# 2.net
KiCad netlist of a schematic drawn in Altium Designer
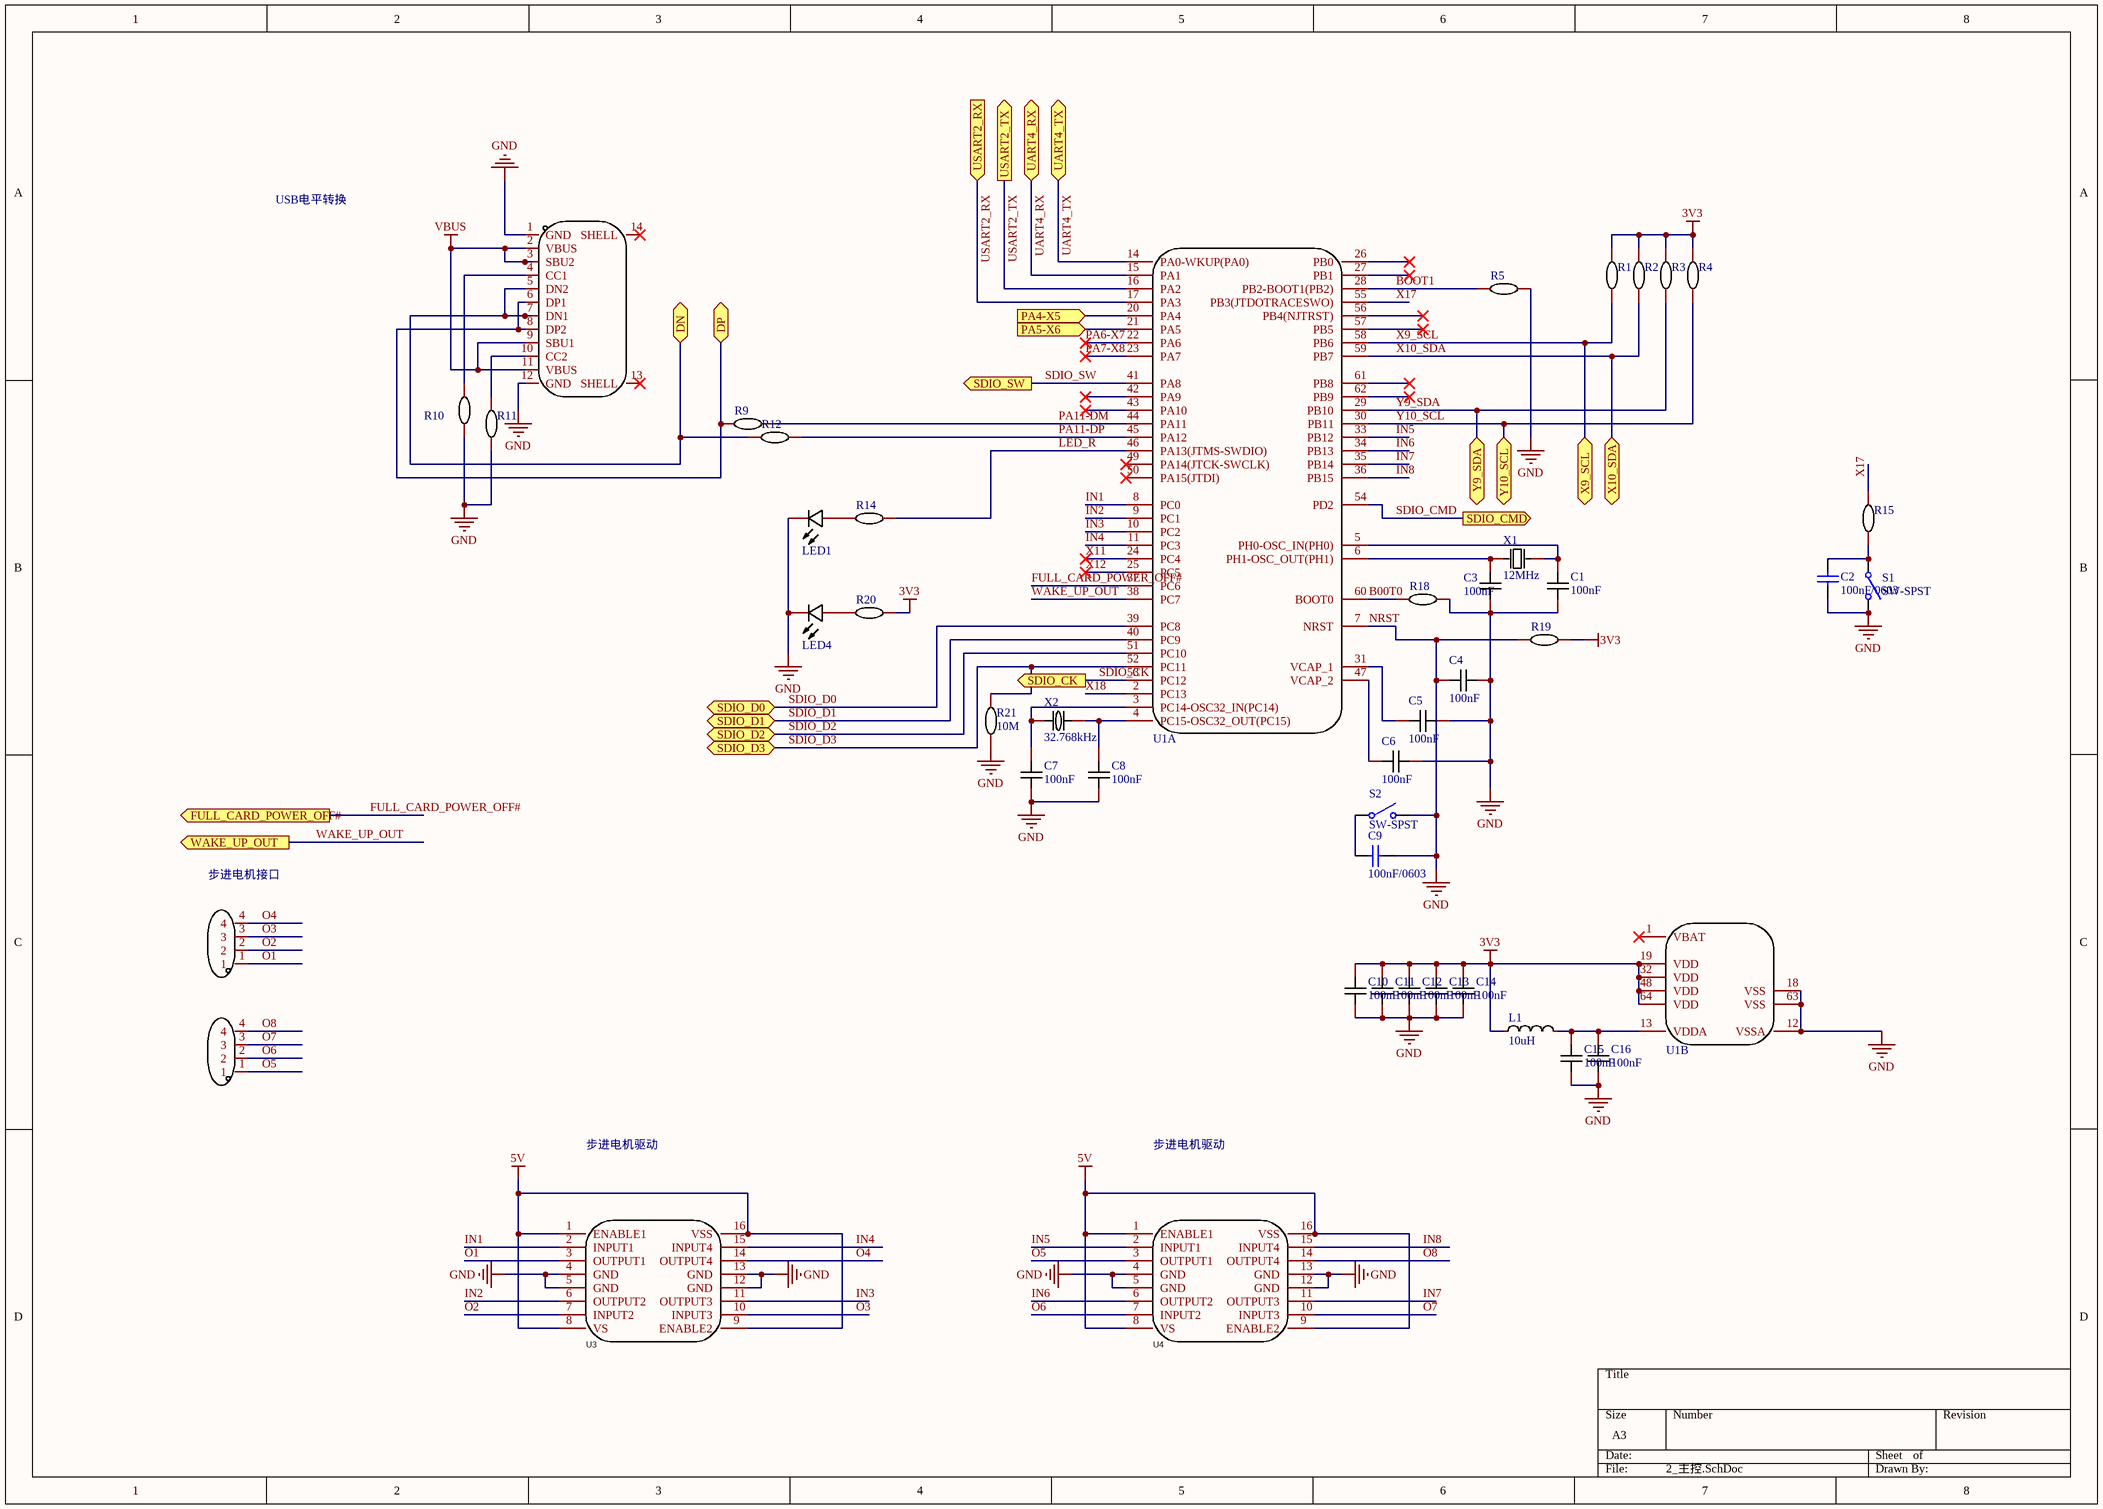
[diagram p0: 2_主控.SchDoc]

(export (version "E")
  (design (tool "Eeschema 10.0.6"))
  (components
    (comp (ref "C1")
      (value "100nF")
      (footprint "0603C")
      (fields (field (name "NAME") "100nF"))
      (libsource (lib "5_CPU_TF卡.schdoc") (part "CAP_0603"))
    )
    (comp (ref "C2")
      (value "100nF/0603")
      (footprint "0603C")
      (description "Capacitor")
      (fields (field (name "PUBLISHER") "Altium Limited"))
      (libsource (lib "MyComponents_v2.5") (part "Cap"))
    )
    (comp (ref "C3")
      (value "100nF")
      (footprint "0603C")
      (fields (field (name "NAME") "100nF"))
      (libsource (lib "5_CPU_TF卡.schdoc") (part "CAP_0603"))
    )
    (comp (ref "C4")
      (value "100nF")
      (footprint "0603C")
      (fields (field (name "NAME") "100nF"))
      (libsource (lib "5_CPU_TF卡.schdoc") (part "CAP_0603"))
    )
    (comp (ref "C5")
      (value "100nF")
      (footprint "0603C")
      (fields (field (name "NAME") "100nF"))
      (libsource (lib "5_CPU_TF卡.schdoc") (part "CAP_0603"))
    )
    (comp (ref "C6")
      (value "100nF")
      (footprint "0603C")
      (fields (field (name "NAME") "100nF"))
      (libsource (lib "5_CPU_TF卡.schdoc") (part "CAP_0603"))
    )
    (comp (ref "C7")
      (value "100nF")
      (footprint "0603C")
      (fields (field (name "NAME") "100nF"))
      (libsource (lib "5_CPU_TF卡.schdoc") (part "CAP_0603"))
    )
    (comp (ref "C8")
      (value "100nF")
      (footprint "0603C")
      (fields (field (name "NAME") "100nF"))
      (libsource (lib "5_CPU_TF卡.schdoc") (part "CAP_0603"))
    )
    (comp (ref "C9")
      (value "100nF/0603")
      (footprint "0603C")
      (description "Capacitor")
      (fields (field (name "PUBLISHER") "Altium Limited"))
      (libsource (lib "MyComponents_v2.5") (part "Cap"))
    )
    (comp (ref "C10")
      (value "100nF")
      (footprint "0402C")
      (fields (field (name "NAME") "100nF"))
      (libsource (lib "5_CPU_TF卡.schdoc") (part "CAP_0603"))
    )
    (comp (ref "C11")
      (value "100nF")
      (footprint "0402C")
      (fields (field (name "NAME") "100nF"))
      (libsource (lib "5_CPU_TF卡.schdoc") (part "CAP_0603"))
    )
    (comp (ref "C12")
      (value "100nF")
      (footprint "0402C")
      (fields (field (name "NAME") "100nF"))
      (libsource (lib "5_CPU_TF卡.schdoc") (part "CAP_0603"))
    )
    (comp (ref "C13")
      (value "100nF")
      (footprint "0402C")
      (fields (field (name "NAME") "100nF"))
      (libsource (lib "5_CPU_TF卡.schdoc") (part "CAP_0603"))
    )
    (comp (ref "C14")
      (value "100nF")
      (footprint "0402C")
      (fields (field (name "NAME") "100nF"))
      (libsource (lib "5_CPU_TF卡.schdoc") (part "CAP_0603"))
    )
    (comp (ref "C15")
      (value "100nF")
      (footprint "0402C")
      (fields (field (name "NAME") "100nF"))
      (libsource (lib "5_CPU_TF卡.schdoc") (part "CAP_0603"))
    )
    (comp (ref "C16")
      (value "100nF")
      (footprint "0402C")
      (fields (field (name "NAME") "100nF"))
      (libsource (lib "5_CPU_TF卡.schdoc") (part "CAP_0603"))
    )
    (comp (ref "CN1")
      (value "HC-XHB-4A")
      (footprint "CONN-TH_4P-P2.50_HCTL_HC-XHB-4A")
      (libsource (lib "HC-XHB-4A1_HC-XHB-4A.schdoc") (part "HC-XHB-4A"))
    )
    (comp (ref "CN2")
      (value "HC-XHB-4A")
      (footprint "CONN-TH_4P-P2.50_HCTL_HC-XHB-4A")
      (libsource (lib "HC-XHB-4A1_HC-XHB-4A.schdoc") (part "HC-XHB-4A"))
    )
    (comp (ref "L1")
      (value "10uH")
      (footprint "L0603")
      (fields (field (name "NAME") "10uH"))
      (libsource (lib "5_CPU_TF卡.schdoc") (part "L_0603"))
    )
    (comp (ref "LED1")
      (value "19-217/BHC-ZL1M2RY/3T")
      (footprint "LED0603-R-RD")
      (libsource (lib "5_CPU_TF卡.schdoc") (part "19-217/BHC-ZL1M2RY/3T"))
    )
    (comp (ref "LED4")
      (value "19-217/BHC-ZL1M2RY/3T")
      (footprint "LED0603-R-RD")
      (libsource (lib "5_CPU_TF卡.schdoc") (part "19-217/BHC-ZL1M2RY/3T"))
    )
    (comp (ref "R1")
      (value "~")
      (footprint "0402R")
      (fields (field (name "MANUFACTURER PART") "RC0402FR-0710KL"))
      (libsource (lib "5_CPU_TF卡.schdoc") (part "RC0402FR-0710KL"))
    )
    (comp (ref "R2")
      (value "~")
      (footprint "0402R")
      (fields (field (name "MANUFACTURER PART") "RC0402FR-0710KL"))
      (libsource (lib "5_CPU_TF卡.schdoc") (part "RC0402FR-0710KL"))
    )
    (comp (ref "R3")
      (value "~")
      (footprint "0402R")
      (fields (field (name "MANUFACTURER PART") "RC0402FR-0710KL"))
      (libsource (lib "5_CPU_TF卡.schdoc") (part "RC0402FR-0710KL"))
    )
    (comp (ref "R4")
      (value "~")
      (footprint "0402R")
      (fields (field (name "MANUFACTURER PART") "RC0402FR-0710KL"))
      (libsource (lib "5_CPU_TF卡.schdoc") (part "RC0402FR-0710KL"))
    )
    (comp (ref "R5")
      (value "~")
      (footprint "0402R")
      (fields (field (name "MANUFACTURER PART") "RC0402FR-0710KL"))
      (libsource (lib "5_CPU_TF卡.schdoc") (part "RC0402FR-0710KL"))
    )
    (comp (ref "R9")
      (value "~")
      (footprint "0402R")
      (fields (field (name "MANUFACTURER PART") "RC0402FR-0710KL"))
      (libsource (lib "5_CPU_TF卡.schdoc") (part "RC0402FR-0710KL"))
    )
    (comp (ref "R10")
      (value "~")
      (footprint "0402R")
      (fields (field (name "MANUFACTURER PART") "RC0402FR-0710KL"))
      (libsource (lib "5_CPU_TF卡.schdoc") (part "RC0402FR-0710KL"))
    )
    (comp (ref "R11")
      (value "~")
      (footprint "0402R")
      (fields (field (name "MANUFACTURER PART") "RC0402FR-0710KL"))
      (libsource (lib "5_CPU_TF卡.schdoc") (part "RC0402FR-0710KL"))
    )
    (comp (ref "R12")
      (value "~")
      (footprint "0402R")
      (fields (field (name "MANUFACTURER PART") "RC0402FR-0710KL"))
      (libsource (lib "5_CPU_TF卡.schdoc") (part "RC0402FR-0710KL"))
    )
    (comp (ref "R14")
      (value "~")
      (footprint "0402R")
      (fields (field (name "MANUFACTURER PART") "RC0402FR-0710KL"))
      (libsource (lib "5_CPU_TF卡.schdoc") (part "RC0402FR-0710KL"))
    )
    (comp (ref "R15")
      (value "~")
      (footprint "0402R")
      (fields (field (name "MANUFACTURER PART") "RC0402FR-0710KL"))
      (libsource (lib "5_CPU_TF卡.schdoc") (part "RC0402FR-0710KL"))
    )
    (comp (ref "R18")
      (value "~")
      (footprint "0402R")
      (fields (field (name "MANUFACTURER PART") "RC0402FR-0710KL"))
      (libsource (lib "5_CPU_TF卡.schdoc") (part "RC0402FR-0710KL"))
    )
    (comp (ref "R19")
      (value "~")
      (footprint "0402R")
      (fields (field (name "MANUFACTURER PART") "RC0402FR-0710KL"))
      (libsource (lib "5_CPU_TF卡.schdoc") (part "RC0402FR-0710KL"))
    )
    (comp (ref "R20")
      (value "~")
      (footprint "0402R")
      (fields (field (name "MANUFACTURER PART") "RC0402FR-0710KL"))
      (libsource (lib "5_CPU_TF卡.schdoc") (part "RC0402FR-0710KL"))
    )
    (comp (ref "R21")
      (value "10M")
      (footprint "0603R")
      (fields (field (name "NAME") "10M"))
      (libsource (lib "5_CPU_TF卡.schdoc") (part "Res_0603"))
    )
    (comp (ref "S1")
      (value "SW-SPST")
      (footprint "SW-3x6mm-SMT")
      (description "Single-Pole, Single-Throw Switch")
      (fields (field (name "PUBLISHER") "Altium Limited"))
      (libsource (lib "MyComponents_v2.5") (part "SW-SPST"))
    )
    (comp (ref "S2")
      (value "SW-SPST")
      (footprint "SW-3x6mm-SMT")
      (description "Single-Pole, Single-Throw Switch")
      (fields (field (name "PUBLISHER") "Altium Limited"))
      (libsource (lib "MyComponents_v2.5") (part "SW-SPST"))
    )
    (comp (ref "U1")
      (value "STM32F405RGT6")
      (footprint "LQFP-64_L10.0-W10.0-P0.50-LS12.0-BL")
      (libsource (lib "5_CPU_TF卡.schdoc") (part "STM32F405RGT6"))
    )
    (comp (ref "U3")
      (value "L293D")
      (footprint "SOIC-20_L13.0-W7.6-P1.27-LS10.3-BL")
      (libsource (lib "L293D1_L293D.schdoc") (part "L293D"))
    )
    (comp (ref "U4")
      (value "L293D")
      (footprint "SOIC-20_L13.0-W7.6-P1.27-LS10.3-BL")
      (libsource (lib "L293D1_L293D.schdoc") (part "L293D"))
    )
    (comp (ref "USB1")
      (value "TYPE-C 16PIN 2MD(073)")
      (footprint "USB-C-SMD_TYPE-C-6PIN-2MD-073")
      (libsource (lib "TYPE-C 16PIN 2MD(073)1_TYPE-C 16PIN 2MD(073).schdoc") (part "TYPE-C 16PIN 2MD(073)"))
    )
    (comp (ref "X1")
      (value "12MHz")
      (footprint "CRYSTAL-SMD_L5.0-W3.2")
      (fields (field (name "MANUFACTURER PART") "X50328MSB2GI") (field (name "NAME") "12MHz"))
      (libsource (lib "5_CPU_TF卡.schdoc") (part "X50328MSB2GI"))
    )
    (comp (ref "X2")
      (value "32.768kHz")
      (footprint "FC-135R_L3.2-W1.5")
      (fields (field (name "MANUFACTURER PART") "Q13FC1350000400") (field (name "NAME") "32.768kHz"))
      (libsource (lib "5_CPU_TF卡.schdoc") (part "Q13FC1350000400"))
    )
  )
  (nets
    (net (code "1") (name "/B00T0") (class "Default")
      (node (ref "R18") (pin "2") (pinfunction "2_2") (pintype "passive"))
      (node (ref "U1") (pin "60") (pinfunction "BOOT0_60") (pintype "passive"))
    )
    (net (code "2") (name "/BOOT1") (class "Default")
      (node (ref "R5") (pin "1") (pinfunction "1_1") (pintype "passive"))
      (node (ref "U1") (pin "28") (pinfunction "PB2-BOOT1(PB2)_28") (pintype "passive"))
    )
    (net (code "3") (name "/DN") (class "Default")
      (node (ref "R12") (pin "2") (pinfunction "2_2") (pintype "passive"))
      (node (ref "USB1") (pin "5") (pinfunction "DN2_5") (pintype "passive"))
      (node (ref "USB1") (pin "7") (pinfunction "DN1_7") (pintype "passive"))
    )
    (net (code "4") (name "/DP") (class "Default")
      (node (ref "R9") (pin "2") (pinfunction "2_2") (pintype "passive"))
      (node (ref "USB1") (pin "6") (pinfunction "DP1_6") (pintype "passive"))
      (node (ref "USB1") (pin "8") (pinfunction "DP2_8") (pintype "passive"))
    )
    (net (code "5") (name "/FULL_CARD_POWER_OFF#") (class "Default")
      (node (ref "U1") (pin "37") (pinfunction "PC6_37") (pintype "passive"))
    )
    (net (code "6") (name "/IN1") (class "Default")
      (node (ref "U1") (pin "8") (pinfunction "PC0_8") (pintype "passive"))
      (node (ref "U3") (pin "2") (pinfunction "INPUT1_2") (pintype "passive"))
    )
    (net (code "7") (name "/IN2") (class "Default")
      (node (ref "U1") (pin "9") (pinfunction "PC1_9") (pintype "passive"))
      (node (ref "U3") (pin "6") (pinfunction "OUTPUT2_6") (pintype "passive"))
    )
    (net (code "8") (name "/IN3") (class "Default")
      (node (ref "U1") (pin "10") (pinfunction "PC2_10") (pintype "passive"))
      (node (ref "U3") (pin "11") (pinfunction "OUTPUT3_11") (pintype "passive"))
    )
    (net (code "9") (name "/IN4") (class "Default")
      (node (ref "U1") (pin "11") (pinfunction "PC3_11") (pintype "passive"))
      (node (ref "U3") (pin "15") (pinfunction "INPUT4_15") (pintype "passive"))
    )
    (net (code "10") (name "/IN5") (class "Default")
      (node (ref "U1") (pin "33") (pinfunction "PB12_33") (pintype "passive"))
      (node (ref "U4") (pin "2") (pinfunction "INPUT1_2") (pintype "passive"))
    )
    (net (code "11") (name "/IN6") (class "Default")
      (node (ref "U1") (pin "34") (pinfunction "PB13_34") (pintype "passive"))
      (node (ref "U4") (pin "6") (pinfunction "OUTPUT2_6") (pintype "passive"))
    )
    (net (code "12") (name "/IN7") (class "Default")
      (node (ref "U1") (pin "35") (pinfunction "PB14_35") (pintype "passive"))
      (node (ref "U4") (pin "11") (pinfunction "OUTPUT3_11") (pintype "passive"))
    )
    (net (code "13") (name "/IN8") (class "Default")
      (node (ref "U1") (pin "36") (pinfunction "PB15_36") (pintype "passive"))
      (node (ref "U4") (pin "15") (pinfunction "INPUT4_15") (pintype "passive"))
    )
    (net (code "14") (name "/LED_R") (class "Default")
      (node (ref "R14") (pin "2") (pinfunction "2_2") (pintype "passive"))
      (node (ref "U1") (pin "46") (pinfunction "PA13(JTMS-SWDIO)_46") (pintype "passive"))
    )
    (net (code "15") (name "/O1") (class "Default")
      (node (ref "CN1") (pin "1") (pinfunction "1_1") (pintype "passive"))
      (node (ref "U3") (pin "3") (pinfunction "OUTPUT1_3") (pintype "passive"))
    )
    (net (code "16") (name "/O2") (class "Default")
      (node (ref "CN1") (pin "2") (pinfunction "2_2") (pintype "passive"))
      (node (ref "U3") (pin "7") (pinfunction "INPUT2_7") (pintype "passive"))
    )
    (net (code "17") (name "/O3") (class "Default")
      (node (ref "CN1") (pin "3") (pinfunction "3_3") (pintype "passive"))
      (node (ref "U3") (pin "10") (pinfunction "INPUT3_10") (pintype "passive"))
    )
    (net (code "18") (name "/O4") (class "Default")
      (node (ref "CN1") (pin "4") (pinfunction "4_4") (pintype "passive"))
      (node (ref "U3") (pin "14") (pinfunction "OUTPUT4_14") (pintype "passive"))
    )
    (net (code "19") (name "/O5") (class "Default")
      (node (ref "CN2") (pin "1") (pinfunction "1_1") (pintype "passive"))
      (node (ref "U4") (pin "3") (pinfunction "OUTPUT1_3") (pintype "passive"))
    )
    (net (code "20") (name "/O6") (class "Default")
      (node (ref "CN2") (pin "2") (pinfunction "2_2") (pintype "passive"))
      (node (ref "U4") (pin "7") (pinfunction "INPUT2_7") (pintype "passive"))
    )
    (net (code "21") (name "/O7") (class "Default")
      (node (ref "CN2") (pin "3") (pinfunction "3_3") (pintype "passive"))
      (node (ref "U4") (pin "10") (pinfunction "INPUT3_10") (pintype "passive"))
    )
    (net (code "22") (name "/O8") (class "Default")
      (node (ref "CN2") (pin "4") (pinfunction "4_4") (pintype "passive"))
      (node (ref "U4") (pin "14") (pinfunction "OUTPUT4_14") (pintype "passive"))
    )
    (net (code "23") (name "/PA4-X5") (class "Default")
      (node (ref "U1") (pin "20") (pinfunction "PA4_20") (pintype "passive"))
    )
    (net (code "24") (name "/PA5-X6") (class "Default")
      (node (ref "U1") (pin "21") (pinfunction "PA5_21") (pintype "passive"))
    )
    (net (code "25") (name "/PA6-X7") (class "Default")
      (node (ref "U1") (pin "22") (pinfunction "PA6_22") (pintype "passive+no_connect"))
    )
    (net (code "26") (name "/PA7-X8") (class "Default")
      (node (ref "U1") (pin "23") (pinfunction "PA7_23") (pintype "passive+no_connect"))
    )
    (net (code "27") (name "/PA11-DM") (class "Default")
      (node (ref "R9") (pin "1") (pinfunction "1_1") (pintype "passive"))
      (node (ref "U1") (pin "44") (pinfunction "PA11_44") (pintype "passive"))
    )
    (net (code "28") (name "/PA11-DP") (class "Default")
      (node (ref "R12") (pin "1") (pinfunction "1_1") (pintype "passive"))
      (node (ref "U1") (pin "45") (pinfunction "PA12_45") (pintype "passive"))
    )
    (net (code "29") (name "/SDIO_CK") (class "Default")
      (node (ref "U1") (pin "53") (pinfunction "PC12_53") (pintype "passive"))
    )
    (net (code "30") (name "/SDIO_CMD") (class "Default")
      (node (ref "U1") (pin "54") (pinfunction "PD2_54") (pintype "passive"))
    )
    (net (code "31") (name "/SDIO_D0") (class "Default")
      (node (ref "U1") (pin "39") (pinfunction "PC8_39") (pintype "passive"))
    )
    (net (code "32") (name "/SDIO_D1") (class "Default")
      (node (ref "U1") (pin "40") (pinfunction "PC9_40") (pintype "passive"))
    )
    (net (code "33") (name "/SDIO_D2") (class "Default")
      (node (ref "U1") (pin "51") (pinfunction "PC10_51") (pintype "passive"))
    )
    (net (code "34") (name "/SDIO_D3") (class "Default")
      (node (ref "R21") (pin "2") (pinfunction "2_2") (pintype "passive"))
      (node (ref "U1") (pin "52") (pinfunction "PC11_52") (pintype "passive"))
    )
    (net (code "35") (name "/SDIO_SW") (class "Default")
      (node (ref "U1") (pin "41") (pinfunction "PA8_41") (pintype "passive"))
    )
    (net (code "36") (name "/UART4_RX") (class "Default")
      (node (ref "U1") (pin "15") (pinfunction "PA1_15") (pintype "passive"))
    )
    (net (code "37") (name "/UART4_TX") (class "Default")
      (node (ref "U1") (pin "14") (pinfunction "PA0-WKUP(PA0)_14") (pintype "passive"))
    )
    (net (code "38") (name "/USART2_RX") (class "Default")
      (node (ref "U1") (pin "17") (pinfunction "PA3_17") (pintype "passive"))
    )
    (net (code "39") (name "/USART2_TX") (class "Default")
      (node (ref "U1") (pin "16") (pinfunction "PA2_16") (pintype "passive"))
    )
    (net (code "40") (name "/WAKE_UP_OUT") (class "Default")
      (node (ref "U1") (pin "38") (pinfunction "PC7_38") (pintype "passive"))
    )
    (net (code "41") (name "/X9_SCL") (class "Default")
      (node (ref "R1") (pin "1") (pinfunction "1_1") (pintype "passive"))
      (node (ref "U1") (pin "58") (pinfunction "PB6_58") (pintype "passive"))
    )
    (net (code "42") (name "/X10_SDA") (class "Default")
      (node (ref "R2") (pin "1") (pinfunction "1_1") (pintype "passive"))
      (node (ref "U1") (pin "59") (pinfunction "PB7_59") (pintype "passive"))
    )
    (net (code "43") (name "/X11") (class "Default")
      (node (ref "U1") (pin "24") (pinfunction "PC4_24") (pintype "passive+no_connect"))
    )
    (net (code "44") (name "/X12") (class "Default")
      (node (ref "U1") (pin "25") (pinfunction "PC5_25") (pintype "passive+no_connect"))
    )
    (net (code "45") (name "/X17") (class "Default")
      (node (ref "R15") (pin "2") (pinfunction "2_2") (pintype "passive"))
      (node (ref "U1") (pin "55") (pinfunction "PB3(JTDOTRACESWO)_55") (pintype "passive"))
    )
    (net (code "46") (name "/X18") (class "Default")
      (node (ref "U1") (pin "2") (pinfunction "PC13_2") (pintype "passive"))
    )
    (net (code "47") (name "/Y9_SDA") (class "Default")
      (node (ref "R3") (pin "1") (pinfunction "1_1") (pintype "passive"))
      (node (ref "U1") (pin "29") (pinfunction "PB10_29") (pintype "passive"))
    )
    (net (code "48") (name "/Y10_SCL") (class "Default")
      (node (ref "R4") (pin "1") (pinfunction "1_1") (pintype "passive"))
      (node (ref "U1") (pin "30") (pinfunction "PB11_30") (pintype "passive"))
    )
    (net (code "49") (name "3V3") (class "Default")
      (node (ref "C10") (pin "2") (pinfunction "2_2") (pintype "passive"))
      (node (ref "C11") (pin "2") (pinfunction "2_2") (pintype "passive"))
      (node (ref "C12") (pin "2") (pinfunction "2_2") (pintype "passive"))
      (node (ref "C13") (pin "2") (pinfunction "2_2") (pintype "passive"))
      (node (ref "C14") (pin "2") (pinfunction "2_2") (pintype "passive"))
      (node (ref "L1") (pin "1") (pinfunction "1_1") (pintype "passive"))
      (node (ref "R1") (pin "2") (pinfunction "2_2") (pintype "passive"))
      (node (ref "R19") (pin "1") (pinfunction "1_1") (pintype "passive"))
      (node (ref "R2") (pin "2") (pinfunction "2_2") (pintype "passive"))
      (node (ref "R20") (pin "1") (pinfunction "1_1") (pintype "passive"))
      (node (ref "R3") (pin "2") (pinfunction "2_2") (pintype "passive"))
      (node (ref "R4") (pin "2") (pinfunction "2_2") (pintype "passive"))
      (node (ref "U1") (pin "19") (pinfunction "VDD_19") (pintype "passive"))
      (node (ref "U1") (pin "32") (pinfunction "VDD_32") (pintype "passive"))
      (node (ref "U1") (pin "48") (pinfunction "VDD_48") (pintype "passive"))
      (node (ref "U1") (pin "64") (pinfunction "VDD_64") (pintype "passive"))
    )
    (net (code "50") (name "5V") (class "Default")
      (node (ref "U3") (pin "1") (pinfunction "ENABLE1_1") (pintype "passive"))
      (node (ref "U3") (pin "16") (pinfunction "VSS_16") (pintype "passive"))
      (node (ref "U3") (pin "8") (pinfunction "VS_8") (pintype "passive"))
      (node (ref "U3") (pin "9") (pinfunction "ENABLE2_9") (pintype "passive"))
      (node (ref "U4") (pin "1") (pinfunction "ENABLE1_1") (pintype "passive"))
      (node (ref "U4") (pin "16") (pinfunction "VSS_16") (pintype "passive"))
      (node (ref "U4") (pin "8") (pinfunction "VS_8") (pintype "passive"))
      (node (ref "U4") (pin "9") (pinfunction "ENABLE2_9") (pintype "passive"))
    )
    (net (code "51") (name "GND") (class "Default")
      (node (ref "C1") (pin "1") (pinfunction "1_1") (pintype "passive"))
      (node (ref "C10") (pin "1") (pinfunction "1_1") (pintype "passive"))
      (node (ref "C11") (pin "1") (pinfunction "1_1") (pintype "passive"))
      (node (ref "C12") (pin "1") (pinfunction "1_1") (pintype "passive"))
      (node (ref "C13") (pin "1") (pinfunction "1_1") (pintype "passive"))
      (node (ref "C14") (pin "1") (pinfunction "1_1") (pintype "passive"))
      (node (ref "C15") (pin "1") (pinfunction "1_1") (pintype "passive"))
      (node (ref "C16") (pin "1") (pinfunction "1_1") (pintype "passive"))
      (node (ref "C2") (pin "2") (pinfunction "2_2") (pintype "passive"))
      (node (ref "C3") (pin "1") (pinfunction "1_1") (pintype "passive"))
      (node (ref "C4") (pin "1") (pinfunction "1_1") (pintype "passive"))
      (node (ref "C4") (pin "2") (pinfunction "2_2") (pintype "passive"))
      (node (ref "C5") (pin "1") (pinfunction "1_1") (pintype "passive"))
      (node (ref "C6") (pin "1") (pinfunction "1_1") (pintype "passive"))
      (node (ref "C7") (pin "1") (pinfunction "1_1") (pintype "passive"))
      (node (ref "C8") (pin "1") (pinfunction "1_1") (pintype "passive"))
      (node (ref "C9") (pin "2") (pinfunction "2_2") (pintype "passive"))
      (node (ref "LED1") (pin "2") (pinfunction "C_2") (pintype "passive"))
      (node (ref "LED4") (pin "2") (pinfunction "C_2") (pintype "passive"))
      (node (ref "R10") (pin "1") (pinfunction "1_1") (pintype "passive"))
      (node (ref "R11") (pin "1") (pinfunction "1_1") (pintype "passive"))
      (node (ref "R18") (pin "1") (pinfunction "1_1") (pintype "passive"))
      (node (ref "R19") (pin "2") (pinfunction "2_2") (pintype "passive"))
      (node (ref "R21") (pin "1") (pinfunction "1_1") (pintype "passive"))
      (node (ref "R5") (pin "2") (pinfunction "2_2") (pintype "passive"))
      (node (ref "S1") (pin "2") (pinfunction "NO_2") (pintype "passive"))
      (node (ref "S2") (pin "2") (pinfunction "NO_2") (pintype "passive"))
      (node (ref "U1") (pin "12") (pinfunction "VSSA_12") (pintype "passive"))
      (node (ref "U1") (pin "18") (pinfunction "VSS_18") (pintype "passive"))
      (node (ref "U1") (pin "63") (pinfunction "VSS_63") (pintype "passive"))
      (node (ref "U1") (pin "7") (pinfunction "NRST_7") (pintype "passive"))
      (node (ref "U3") (pin "12") (pinfunction "GND_12") (pintype "passive"))
      (node (ref "U3") (pin "13") (pinfunction "GND_13") (pintype "passive"))
      (node (ref "U3") (pin "4") (pinfunction "GND_4") (pintype "passive"))
      (node (ref "U3") (pin "5") (pinfunction "GND_5") (pintype "passive"))
      (node (ref "U4") (pin "12") (pinfunction "GND_12") (pintype "passive"))
      (node (ref "U4") (pin "13") (pinfunction "GND_13") (pintype "passive"))
      (node (ref "U4") (pin "4") (pinfunction "GND_4") (pintype "passive"))
      (node (ref "U4") (pin "5") (pinfunction "GND_5") (pintype "passive"))
      (node (ref "USB1") (pin "1") (pinfunction "GND_1") (pintype "passive"))
      (node (ref "USB1") (pin "12") (pinfunction "GND_12") (pintype "passive"))
    )
    (net (code "52") (name "Net-(LED1-A)") (class "Default")
      (node (ref "LED1") (pin "1") (pinfunction "A_1") (pintype "passive"))
      (node (ref "R14") (pin "1") (pinfunction "1_1") (pintype "passive"))
    )
    (net (code "53") (name "Net-(LED4-A)") (class "Default")
      (node (ref "LED4") (pin "1") (pinfunction "A_1") (pintype "passive"))
      (node (ref "R20") (pin "2") (pinfunction "2_2") (pintype "passive"))
    )
    (net (code "54") (name "Net-(S1-COMMON)") (class "Default")
      (node (ref "C2") (pin "1") (pinfunction "1_1") (pintype "passive"))
      (node (ref "R15") (pin "1") (pinfunction "1_1") (pintype "passive"))
      (node (ref "S1") (pin "1") (pinfunction "COMMON_1") (pintype "passive"))
    )
    (net (code "55") (name "Net-(S2-COMMON)") (class "Default")
      (node (ref "C9") (pin "1") (pinfunction "1_1") (pintype "passive"))
      (node (ref "S2") (pin "1") (pinfunction "COMMON_1") (pintype "passive"))
    )
    (net (code "56") (name "Net-(U1A-PC14-OSC32_IN(PC14))") (class "Default")
      (node (ref "C7") (pin "2") (pinfunction "2_2") (pintype "passive"))
      (node (ref "U1") (pin "3") (pinfunction "PC14-OSC32_IN(PC14)_3") (pintype "passive"))
      (node (ref "X2") (pin "1") (pinfunction "1_1") (pintype "passive"))
    )
    (net (code "57") (name "Net-(U1A-PC15-OSC32_OUT(PC15))") (class "Default")
      (node (ref "C8") (pin "2") (pinfunction "2_2") (pintype "passive"))
      (node (ref "U1") (pin "4") (pinfunction "PC15-OSC32_OUT(PC15)_4") (pintype "passive"))
      (node (ref "X2") (pin "2") (pinfunction "2_2") (pintype "passive"))
    )
    (net (code "58") (name "Net-(U1A-PH0-OSC_IN(PH0))") (class "Default")
      (node (ref "C1") (pin "2") (pinfunction "2_2") (pintype "passive"))
      (node (ref "U1") (pin "5") (pinfunction "PH0-OSC_IN(PH0)_5") (pintype "passive"))
      (node (ref "X1") (pin "2") (pinfunction "OSC2_2") (pintype "passive"))
    )
    (net (code "59") (name "Net-(U1A-PH1-OSC_OUT(PH1))") (class "Default")
      (node (ref "C3") (pin "2") (pinfunction "2_2") (pintype "passive"))
      (node (ref "U1") (pin "6") (pinfunction "PH1-OSC_OUT(PH1)_6") (pintype "passive"))
      (node (ref "X1") (pin "1") (pinfunction "OSC1_1") (pintype "passive"))
    )
    (net (code "60") (name "Net-(U1A-VCAP_1)") (class "Default")
      (node (ref "C5") (pin "2") (pinfunction "2_2") (pintype "passive"))
      (node (ref "U1") (pin "31") (pinfunction "VCAP_1_31") (pintype "passive"))
    )
    (net (code "61") (name "Net-(U1A-VCAP_2)") (class "Default")
      (node (ref "C6") (pin "2") (pinfunction "2_2") (pintype "passive"))
      (node (ref "U1") (pin "47") (pinfunction "VCAP_2_47") (pintype "passive"))
    )
    (net (code "62") (name "Net-(U1B-VDDA)") (class "Default")
      (node (ref "C15") (pin "2") (pinfunction "2_2") (pintype "passive"))
      (node (ref "C16") (pin "2") (pinfunction "2_2") (pintype "passive"))
      (node (ref "L1") (pin "2") (pinfunction "2_2") (pintype "passive"))
      (node (ref "U1") (pin "13") (pinfunction "VDDA_13") (pintype "passive"))
    )
    (net (code "63") (name "Net-(USB1-CC1)") (class "Default")
      (node (ref "R10") (pin "2") (pinfunction "2_2") (pintype "passive"))
      (node (ref "USB1") (pin "4") (pinfunction "CC1_4") (pintype "passive"))
    )
    (net (code "64") (name "Net-(USB1-CC2)") (class "Default")
      (node (ref "R11") (pin "2") (pinfunction "2_2") (pintype "passive"))
      (node (ref "USB1") (pin "10") (pinfunction "CC2_10") (pintype "passive"))
    )
    (net (code "65") (name "VBUS") (class "Default")
      (node (ref "USB1") (pin "11") (pinfunction "VBUS_11") (pintype "passive"))
      (node (ref "USB1") (pin "2") (pinfunction "VBUS_2") (pintype "passive"))
      (node (ref "USB1") (pin "3") (pinfunction "SBU2_3") (pintype "passive"))
      (node (ref "USB1") (pin "9") (pinfunction "SBU1_9") (pintype "passive"))
    )
    (net (code "66") (name "unconnected-(U1A-PA9-Pad42)") (class "Default")
      (node (ref "U1") (pin "42") (pinfunction "PA9_42") (pintype "passive+no_connect"))
    )
    (net (code "67") (name "unconnected-(U1A-PA10-Pad43)") (class "Default")
      (node (ref "U1") (pin "43") (pinfunction "PA10_43") (pintype "passive+no_connect"))
    )
    (net (code "68") (name "unconnected-(U1A-PA14(JTCK-SWCLK)-Pad49)") (class "Default")
      (node (ref "U1") (pin "49") (pinfunction "PA14(JTCK-SWCLK)_49") (pintype "passive+no_connect"))
    )
    (net (code "69") (name "unconnected-(U1A-PA15(JTDI)-Pad50)") (class "Default")
      (node (ref "U1") (pin "50") (pinfunction "PA15(JTDI)_50") (pintype "passive+no_connect"))
    )
    (net (code "70") (name "unconnected-(U1A-PB0-Pad26)") (class "Default")
      (node (ref "U1") (pin "26") (pinfunction "PB0_26") (pintype "passive+no_connect"))
    )
    (net (code "71") (name "unconnected-(U1A-PB1-Pad27)") (class "Default")
      (node (ref "U1") (pin "27") (pinfunction "PB1_27") (pintype "passive+no_connect"))
    )
    (net (code "72") (name "unconnected-(U1A-PB4(NJTRST)-Pad56)") (class "Default")
      (node (ref "U1") (pin "56") (pinfunction "PB4(NJTRST)_56") (pintype "passive+no_connect"))
    )
    (net (code "73") (name "unconnected-(U1A-PB5-Pad57)") (class "Default")
      (node (ref "U1") (pin "57") (pinfunction "PB5_57") (pintype "passive+no_connect"))
    )
    (net (code "74") (name "unconnected-(U1A-PB8-Pad61)") (class "Default")
      (node (ref "U1") (pin "61") (pinfunction "PB8_61") (pintype "passive+no_connect"))
    )
    (net (code "75") (name "unconnected-(U1A-PB9-Pad62)") (class "Default")
      (node (ref "U1") (pin "62") (pinfunction "PB9_62") (pintype "passive+no_connect"))
    )
    (net (code "76") (name "unconnected-(U1B-VBAT-Pad1)") (class "Default")
      (node (ref "U1") (pin "1") (pinfunction "VBAT_1") (pintype "passive+no_connect"))
    )
    (net (code "77") (name "unconnected-(USB1-SHELL-Pad13)") (class "Default")
      (node (ref "USB1") (pin "13") (pinfunction "SHELL_13") (pintype "passive+no_connect"))
    )
    (net (code "78") (name "unconnected-(USB1-SHELL-Pad14)") (class "Default")
      (node (ref "USB1") (pin "14") (pinfunction "SHELL_14") (pintype "passive+no_connect"))
    )
  )
)
